# 04-RS422-2.net
KiCad netlist of a schematic drawn in Altium Designer
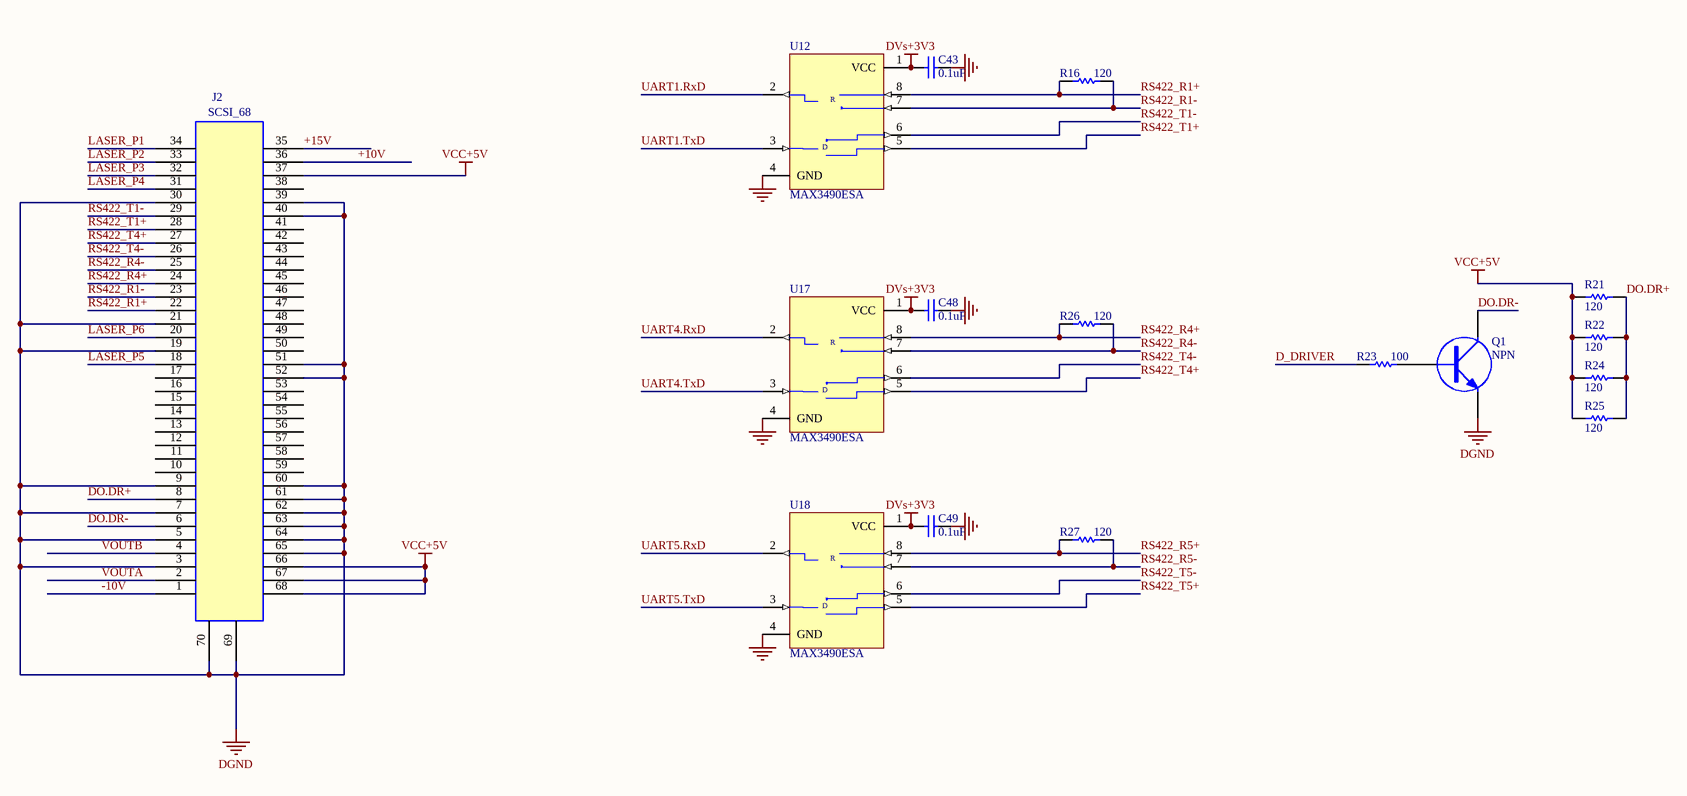
[diagram p0: 04-RS422-2.SchDoc]

(export (version "E")
  (design (tool "Eeschema 10.0.6"))
  (components
    (comp (ref "C43")
      (value "0.1uF")
      (footprint "CR1608-0603")
      (description "X7R")
      (fields (field (name "PUBLISHER") "Altium Limited"))
      (libsource (lib "Miscellaneous Devices") (part "Cap"))
    )
    (comp (ref "C48")
      (value "0.1uF")
      (footprint "CR1608-0603")
      (description "X7R")
      (fields (field (name "PUBLISHER") "Altium Limited"))
      (libsource (lib "Miscellaneous Devices") (part "Cap"))
    )
    (comp (ref "C49")
      (value "0.1uF")
      (footprint "CR1608-0603")
      (description "X7R")
      (fields (field (name "PUBLISHER") "Altium Limited"))
      (libsource (lib "Miscellaneous Devices") (part "Cap"))
    )
    (comp (ref "J2") (value "SCSI_68") (footprint "SCSI68") (libsource (lib "原理图库") (part "SCSI68")))
    (comp (ref "Q1")
      (value "NPN")
      (footprint "3DG130BJ_NPN")
      (description "NPN Transistor")
      (libsource (lib "RS232Ctrl_Int") (part "NPN"))
    )
    (comp (ref "R16")
      (value "120")
      (footprint "CR3216-1206")
      (description "Resistor")
      (fields (field (name "PUBLISHER") "Altium Limited"))
      (libsource (lib "Miscellaneous Devices") (part "Res1"))
    )
    (comp (ref "R21")
      (value "120")
      (footprint "CR3216-1206")
      (description "Resistor")
      (fields (field (name "PUBLISHER") "Altium Limited"))
      (libsource (lib "Miscellaneous Devices") (part "Res1"))
    )
    (comp (ref "R22")
      (value "120")
      (footprint "CR3216-1206")
      (description "Resistor")
      (fields (field (name "PUBLISHER") "Altium Limited"))
      (libsource (lib "Miscellaneous Devices") (part "Res1"))
    )
    (comp (ref "R23")
      (value "100")
      (footprint "0805-X")
      (description "Resistor")
      (fields (field (name "PUBLISHER") "Altium Limited"))
      (libsource (lib "Miscellaneous Devices") (part "Res1"))
    )
    (comp (ref "R24")
      (value "120")
      (footprint "CR3216-1206")
      (description "Resistor")
      (fields (field (name "PUBLISHER") "Altium Limited"))
      (libsource (lib "Miscellaneous Devices") (part "Res1"))
    )
    (comp (ref "R25")
      (value "120")
      (footprint "CR3216-1206")
      (description "Resistor")
      (fields (field (name "PUBLISHER") "Altium Limited"))
      (libsource (lib "Miscellaneous Devices") (part "Res1"))
    )
    (comp (ref "R26")
      (value "120")
      (footprint "CR3216-1206")
      (description "Resistor")
      (fields (field (name "PUBLISHER") "Altium Limited"))
      (libsource (lib "Miscellaneous Devices") (part "Res1"))
    )
    (comp (ref "R27")
      (value "120")
      (footprint "CR3216-1206")
      (description "Resistor")
      (fields (field (name "PUBLISHER") "Altium Limited"))
      (libsource (lib "Miscellaneous Devices") (part "Res1"))
    )
    (comp (ref "U12")
      (value "MAX3490ESA")
      (footprint "SO8.W=6.0")
      (description "Low-Power, Slew-Rate-Limited RS-485/RS-422 Transceiver")
      (fields (field (name "PUBLISHER") "Altium Limited"))
      (libsource (lib "Maxim Communication Transceiver") (part "MAX488ESA"))
    )
    (comp (ref "U17")
      (value "MAX3490ESA")
      (footprint "SO8.W=6.0")
      (description "Low-Power, Slew-Rate-Limited RS-485/RS-422 Transceiver")
      (fields (field (name "PUBLISHER") "Altium Limited"))
      (libsource (lib "Maxim Communication Transceiver") (part "MAX488ESA"))
    )
    (comp (ref "U18")
      (value "MAX3490ESA")
      (footprint "SO8.W=6.0")
      (description "Low-Power, Slew-Rate-Limited RS-485/RS-422 Transceiver")
      (fields (field (name "PUBLISHER") "Altium Limited"))
      (libsource (lib "Maxim Communication Transceiver") (part "MAX488ESA"))
    )
  )
  (nets
    (net (code "1") (name "/+10V") (class "Default")
      (node (ref "J2") (pin "36") (pinfunction "36_36") (pintype "passive"))
    )
    (net (code "2") (name "/+15V") (class "Default")
      (node (ref "J2") (pin "35") (pinfunction "35_35") (pintype "passive"))
    )
    (net (code "3") (name "/-10V") (class "Default")
      (node (ref "J2") (pin "1") (pinfunction "1_1") (pintype "passive"))
    )
    (net (code "4") (name "/DO.DR+") (class "Default")
      (node (ref "J2") (pin "8") (pinfunction "8_8") (pintype "passive"))
      (node (ref "R21") (pin "2") (pinfunction "2_2") (pintype "passive"))
      (node (ref "R22") (pin "2") (pinfunction "2_2") (pintype "passive"))
      (node (ref "R24") (pin "2") (pinfunction "2_2") (pintype "passive"))
      (node (ref "R25") (pin "2") (pinfunction "2_2") (pintype "passive"))
    )
    (net (code "5") (name "/DO.DR-") (class "Default")
      (node (ref "J2") (pin "6") (pinfunction "6_6") (pintype "passive"))
      (node (ref "Q1") (pin "2") (pinfunction "C_2") (pintype "passive"))
    )
    (net (code "6") (name "/D_DRIVER") (class "Default")
      (node (ref "R23") (pin "2") (pinfunction "2_2") (pintype "passive"))
    )
    (net (code "7") (name "/LASER_P1") (class "Default")
      (node (ref "J2") (pin "34") (pinfunction "34_34") (pintype "passive"))
    )
    (net (code "8") (name "/LASER_P2") (class "Default")
      (node (ref "J2") (pin "33") (pinfunction "33_33") (pintype "passive"))
    )
    (net (code "9") (name "/LASER_P3") (class "Default")
      (node (ref "J2") (pin "32") (pinfunction "32_32") (pintype "passive"))
    )
    (net (code "10") (name "/LASER_P4") (class "Default")
      (node (ref "J2") (pin "31") (pinfunction "31_31") (pintype "passive"))
    )
    (net (code "11") (name "/LASER_P5") (class "Default")
      (node (ref "J2") (pin "18") (pinfunction "18_18") (pintype "passive"))
    )
    (net (code "12") (name "/LASER_P6") (class "Default")
      (node (ref "J2") (pin "20") (pinfunction "20_20") (pintype "passive"))
    )
    (net (code "13") (name "/RS422_R1+") (class "Default")
      (node (ref "J2") (pin "22") (pinfunction "22_22") (pintype "passive"))
      (node (ref "R16") (pin "2") (pinfunction "2_2") (pintype "passive"))
      (node (ref "U12") (pin "8") (pinfunction "A_8") (pintype "input"))
    )
    (net (code "14") (name "/RS422_R1-") (class "Default")
      (node (ref "J2") (pin "23") (pinfunction "23_23") (pintype "passive"))
      (node (ref "R16") (pin "1") (pinfunction "1_1") (pintype "passive"))
      (node (ref "U12") (pin "7") (pinfunction "B_7") (pintype "input"))
    )
    (net (code "15") (name "/RS422_R4+") (class "Default")
      (node (ref "J2") (pin "24") (pinfunction "24_24") (pintype "passive"))
      (node (ref "R26") (pin "2") (pinfunction "2_2") (pintype "passive"))
      (node (ref "U17") (pin "8") (pinfunction "A_8") (pintype "input"))
    )
    (net (code "16") (name "/RS422_R4-") (class "Default")
      (node (ref "J2") (pin "25") (pinfunction "25_25") (pintype "passive"))
      (node (ref "R26") (pin "1") (pinfunction "1_1") (pintype "passive"))
      (node (ref "U17") (pin "7") (pinfunction "B_7") (pintype "input"))
    )
    (net (code "17") (name "/RS422_R5+") (class "Default")
      (node (ref "R27") (pin "2") (pinfunction "2_2") (pintype "passive"))
      (node (ref "U18") (pin "8") (pinfunction "A_8") (pintype "input"))
    )
    (net (code "18") (name "/RS422_R5-") (class "Default")
      (node (ref "R27") (pin "1") (pinfunction "1_1") (pintype "passive"))
      (node (ref "U18") (pin "7") (pinfunction "B_7") (pintype "input"))
    )
    (net (code "19") (name "/RS422_T1+") (class "Default")
      (node (ref "J2") (pin "28") (pinfunction "28_28") (pintype "passive"))
      (node (ref "U12") (pin "5") (pinfunction "Y_5") (pintype "output"))
    )
    (net (code "20") (name "/RS422_T1-") (class "Default")
      (node (ref "J2") (pin "29") (pinfunction "29_29") (pintype "passive"))
      (node (ref "U12") (pin "6") (pinfunction "Z_6") (pintype "output"))
    )
    (net (code "21") (name "/RS422_T4+") (class "Default")
      (node (ref "J2") (pin "27") (pinfunction "27_27") (pintype "passive"))
      (node (ref "U17") (pin "5") (pinfunction "Y_5") (pintype "output"))
    )
    (net (code "22") (name "/RS422_T4-") (class "Default")
      (node (ref "J2") (pin "26") (pinfunction "26_26") (pintype "passive"))
      (node (ref "U17") (pin "6") (pinfunction "Z_6") (pintype "output"))
    )
    (net (code "23") (name "/RS422_T5+") (class "Default")
      (node (ref "U18") (pin "5") (pinfunction "Y_5") (pintype "output"))
    )
    (net (code "24") (name "/RS422_T5-") (class "Default")
      (node (ref "U18") (pin "6") (pinfunction "Z_6") (pintype "output"))
    )
    (net (code "25") (name "/UART1.RxD") (class "Default")
      (node (ref "U12") (pin "2") (pinfunction "RO_2") (pintype "output"))
    )
    (net (code "26") (name "/UART1.TxD") (class "Default")
      (node (ref "U12") (pin "3") (pinfunction "DI_3") (pintype "input"))
    )
    (net (code "27") (name "/UART4.RxD") (class "Default")
      (node (ref "U17") (pin "2") (pinfunction "RO_2") (pintype "output"))
    )
    (net (code "28") (name "/UART4.TxD") (class "Default")
      (node (ref "U17") (pin "3") (pinfunction "DI_3") (pintype "input"))
    )
    (net (code "29") (name "/UART5.RxD") (class "Default")
      (node (ref "U18") (pin "2") (pinfunction "RO_2") (pintype "output"))
    )
    (net (code "30") (name "/UART5.TxD") (class "Default")
      (node (ref "U18") (pin "3") (pinfunction "DI_3") (pintype "input"))
    )
    (net (code "31") (name "/VOUTA") (class "Default")
      (node (ref "J2") (pin "2") (pinfunction "2_2") (pintype "passive"))
    )
    (net (code "32") (name "/VOUTB") (class "Default")
      (node (ref "J2") (pin "4") (pinfunction "4_4") (pintype "passive"))
    )
    (net (code "33") (name "DGND") (class "Default")
      (node (ref "C43") (pin "2") (pinfunction "2_2") (pintype "passive"))
      (node (ref "C48") (pin "2") (pinfunction "2_2") (pintype "passive"))
      (node (ref "C49") (pin "2") (pinfunction "2_2") (pintype "passive"))
      (node (ref "J2") (pin "19") (pinfunction "19_19") (pintype "passive"))
      (node (ref "J2") (pin "21") (pinfunction "21_21") (pintype "passive"))
      (node (ref "J2") (pin "3") (pinfunction "3_3") (pintype "passive"))
      (node (ref "J2") (pin "30") (pinfunction "30_30") (pintype "passive"))
      (node (ref "J2") (pin "39") (pinfunction "39_39") (pintype "passive"))
      (node (ref "J2") (pin "40") (pinfunction "40_40") (pintype "passive"))
      (node (ref "J2") (pin "5") (pinfunction "5_5") (pintype "passive"))
      (node (ref "J2") (pin "51") (pinfunction "51_51") (pintype "passive"))
      (node (ref "J2") (pin "52") (pinfunction "52_52") (pintype "passive"))
      (node (ref "J2") (pin "60") (pinfunction "60_60") (pintype "passive"))
      (node (ref "J2") (pin "61") (pinfunction "61_61") (pintype "passive"))
      (node (ref "J2") (pin "62") (pinfunction "62_62") (pintype "passive"))
      (node (ref "J2") (pin "63") (pinfunction "63_63") (pintype "passive"))
      (node (ref "J2") (pin "64") (pinfunction "64_64") (pintype "passive"))
      (node (ref "J2") (pin "65") (pinfunction "65_65") (pintype "passive"))
      (node (ref "J2") (pin "69") (pinfunction "69_69") (pintype "passive"))
      (node (ref "J2") (pin "7") (pinfunction "7_7") (pintype "passive"))
      (node (ref "J2") (pin "70") (pinfunction "70_70") (pintype "passive"))
      (node (ref "J2") (pin "9") (pinfunction "9_9") (pintype "passive"))
      (node (ref "Q1") (pin "3") (pinfunction "E_3") (pintype "passive"))
      (node (ref "U12") (pin "4") (pinfunction "GND_4") (pintype "power_in"))
      (node (ref "U17") (pin "4") (pinfunction "GND_4") (pintype "power_in"))
      (node (ref "U18") (pin "4") (pinfunction "GND_4") (pintype "power_in"))
    )
    (net (code "34") (name "DVs+3V3") (class "Default")
      (node (ref "C43") (pin "1") (pinfunction "1_1") (pintype "passive"))
      (node (ref "C48") (pin "1") (pinfunction "1_1") (pintype "passive"))
      (node (ref "C49") (pin "1") (pinfunction "1_1") (pintype "passive"))
      (node (ref "U12") (pin "1") (pinfunction "VCC_1") (pintype "power_in"))
      (node (ref "U17") (pin "1") (pinfunction "VCC_1") (pintype "power_in"))
      (node (ref "U18") (pin "1") (pinfunction "VCC_1") (pintype "power_in"))
    )
    (net (code "35") (name "Net-(Q1-B)") (class "Default")
      (node (ref "Q1") (pin "1") (pinfunction "B_1") (pintype "passive"))
      (node (ref "R23") (pin "1") (pinfunction "1_1") (pintype "passive"))
    )
    (net (code "36") (name "VCC+5V") (class "Default")
      (node (ref "J2") (pin "37") (pinfunction "37_37") (pintype "passive"))
      (node (ref "J2") (pin "66") (pinfunction "66_66") (pintype "passive"))
      (node (ref "J2") (pin "67") (pinfunction "67_67") (pintype "passive"))
      (node (ref "J2") (pin "68") (pinfunction "68_68") (pintype "passive"))
      (node (ref "R21") (pin "1") (pinfunction "1_1") (pintype "passive"))
      (node (ref "R22") (pin "1") (pinfunction "1_1") (pintype "passive"))
      (node (ref "R24") (pin "1") (pinfunction "1_1") (pintype "passive"))
      (node (ref "R25") (pin "1") (pinfunction "1_1") (pintype "passive"))
    )
    (net (code "37") (name "unconnected-(J2-Pad10)") (class "Default")
      (node (ref "J2") (pin "10") (pinfunction "10_10") (pintype "passive"))
    )
    (net (code "38") (name "unconnected-(J2-Pad11)") (class "Default")
      (node (ref "J2") (pin "11") (pinfunction "11_11") (pintype "passive"))
    )
    (net (code "39") (name "unconnected-(J2-Pad12)") (class "Default")
      (node (ref "J2") (pin "12") (pinfunction "12_12") (pintype "passive"))
    )
    (net (code "40") (name "unconnected-(J2-Pad13)") (class "Default")
      (node (ref "J2") (pin "13") (pinfunction "13_13") (pintype "passive"))
    )
    (net (code "41") (name "unconnected-(J2-Pad14)") (class "Default")
      (node (ref "J2") (pin "14") (pinfunction "14_14") (pintype "passive"))
    )
    (net (code "42") (name "unconnected-(J2-Pad15)") (class "Default")
      (node (ref "J2") (pin "15") (pinfunction "15_15") (pintype "passive"))
    )
    (net (code "43") (name "unconnected-(J2-Pad16)") (class "Default")
      (node (ref "J2") (pin "16") (pinfunction "16_16") (pintype "passive"))
    )
    (net (code "44") (name "unconnected-(J2-Pad17)") (class "Default")
      (node (ref "J2") (pin "17") (pinfunction "17_17") (pintype "passive"))
    )
    (net (code "45") (name "unconnected-(J2-Pad38)") (class "Default")
      (node (ref "J2") (pin "38") (pinfunction "38_38") (pintype "passive"))
    )
    (net (code "46") (name "unconnected-(J2-Pad41)") (class "Default")
      (node (ref "J2") (pin "41") (pinfunction "41_41") (pintype "passive"))
    )
    (net (code "47") (name "unconnected-(J2-Pad42)") (class "Default")
      (node (ref "J2") (pin "42") (pinfunction "42_42") (pintype "passive"))
    )
    (net (code "48") (name "unconnected-(J2-Pad43)") (class "Default")
      (node (ref "J2") (pin "43") (pinfunction "43_43") (pintype "passive"))
    )
    (net (code "49") (name "unconnected-(J2-Pad44)") (class "Default")
      (node (ref "J2") (pin "44") (pinfunction "44_44") (pintype "passive"))
    )
    (net (code "50") (name "unconnected-(J2-Pad45)") (class "Default")
      (node (ref "J2") (pin "45") (pinfunction "45_45") (pintype "passive"))
    )
    (net (code "51") (name "unconnected-(J2-Pad46)") (class "Default")
      (node (ref "J2") (pin "46") (pinfunction "46_46") (pintype "passive"))
    )
    (net (code "52") (name "unconnected-(J2-Pad47)") (class "Default")
      (node (ref "J2") (pin "47") (pinfunction "47_47") (pintype "passive"))
    )
    (net (code "53") (name "unconnected-(J2-Pad48)") (class "Default")
      (node (ref "J2") (pin "48") (pinfunction "48_48") (pintype "passive"))
    )
    (net (code "54") (name "unconnected-(J2-Pad49)") (class "Default")
      (node (ref "J2") (pin "49") (pinfunction "49_49") (pintype "passive"))
    )
    (net (code "55") (name "unconnected-(J2-Pad50)") (class "Default")
      (node (ref "J2") (pin "50") (pinfunction "50_50") (pintype "passive"))
    )
    (net (code "56") (name "unconnected-(J2-Pad53)") (class "Default")
      (node (ref "J2") (pin "53") (pinfunction "53_53") (pintype "passive"))
    )
    (net (code "57") (name "unconnected-(J2-Pad54)") (class "Default")
      (node (ref "J2") (pin "54") (pinfunction "54_54") (pintype "passive"))
    )
    (net (code "58") (name "unconnected-(J2-Pad55)") (class "Default")
      (node (ref "J2") (pin "55") (pinfunction "55_55") (pintype "passive"))
    )
    (net (code "59") (name "unconnected-(J2-Pad56)") (class "Default")
      (node (ref "J2") (pin "56") (pinfunction "56_56") (pintype "passive"))
    )
    (net (code "60") (name "unconnected-(J2-Pad57)") (class "Default")
      (node (ref "J2") (pin "57") (pinfunction "57_57") (pintype "passive"))
    )
    (net (code "61") (name "unconnected-(J2-Pad58)") (class "Default")
      (node (ref "J2") (pin "58") (pinfunction "58_58") (pintype "passive"))
    )
    (net (code "62") (name "unconnected-(J2-Pad59)") (class "Default")
      (node (ref "J2") (pin "59") (pinfunction "59_59") (pintype "passive"))
    )
  )
)
